# SCH_Syntheseproject_proof_of_concept_sen.net
KiCad netlist of a schematic drawn in EasyEDA
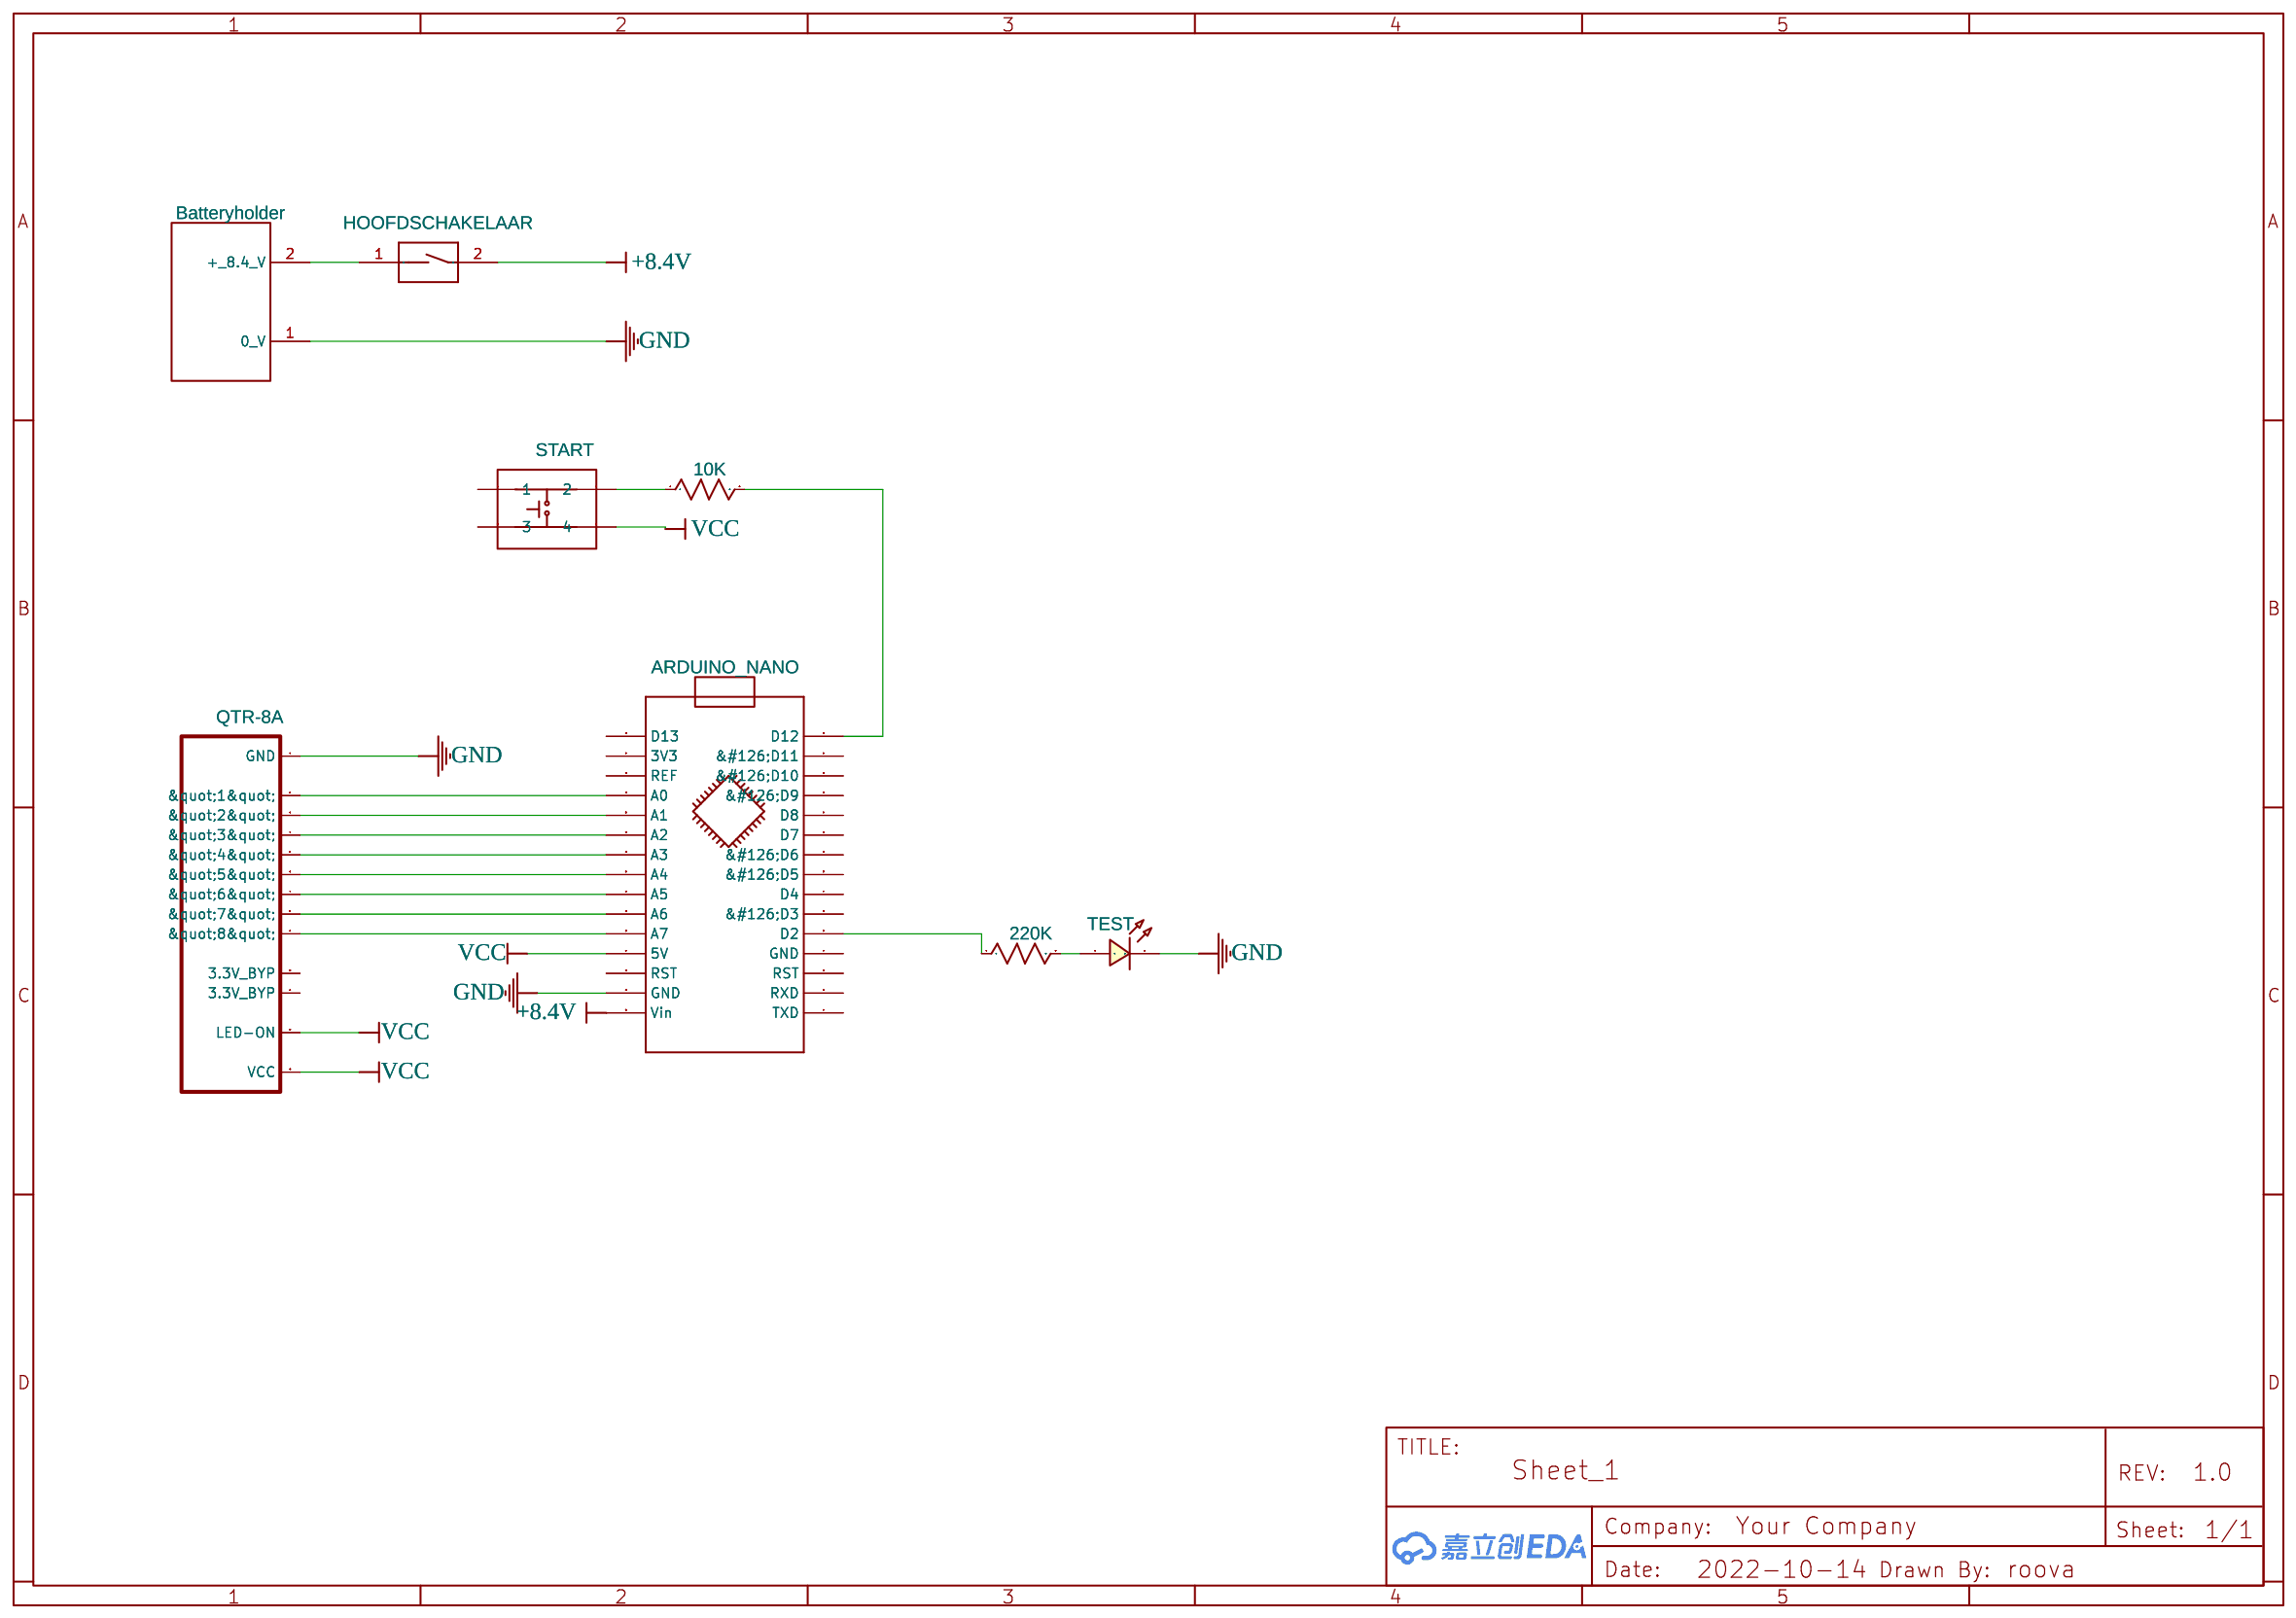
[diagram p0: schematic sheet]

(export (version "E")
  (design (tool "Eeschema 10.0.6"))
  (components
    (comp (ref "10K") (value "1k") (libsource (lib "") (part "R_0603_US_1")))
    (comp (ref "220K") (value "1k") (libsource (lib "") (part "R_0603_US")))
    (comp (ref "ARDUINO_NANO")
      (value "ARDUINO-NANO_V3")
      (fields (field (name "BOM_Manufacturer Part") "ARDUINO-NANO_AK"))
      (libsource (lib "") (part "ARDUINO-NANO_V3"))
    )
    (comp (ref "HOOFDSCHAKELAAR")
      (value "DIP1")
      (fields
        (field (name "BOM_Manufacturer Part") "A6TN-1101")
        (field (name "BOM_Supplier Part") "Z12167-ND")
      )
      (libsource (lib "") (part "DIP1"))
    )
    (comp (ref "START")
      (value "PUSHBUTTON 6X6X4.5 4 PINS COPY")
      (fields (field (name "BOM_Manufacturer Part") "sparkfun"))
      (libsource (lib "") (part "PUSHBUTTON 6X6X4.5 4 PINS COPY"))
    )
    (comp (ref "TEST")
      (value "LED-0603_R")
      (fields
        (field (name "BOM_Manufacturer Part") "19-217/R6C-AL1M2VY/3T")
        (field (name "BOM_Supplier Part") "C72044")
      )
      (libsource (lib "") (part "LED-0603_R"))
    )
    (comp (ref "U2")
      (value "QTR-8A")
      (fields (field (name "BOM_Supplier Part") "960"))
      (libsource (lib "") (part "QTR-8A"))
    )
    (comp (ref "U4") (value "Batteryholder") (libsource (lib "") (part "Batteryholder")))
  )
  (nets
    (net (code "1") (name "+8.4V") (class "Default")
      (node (ref "ARDUINO_NANO") (pin "30") (pinfunction "Vin_30") (pintype "unspecified"))
      (node (ref "HOOFDSCHAKELAAR") (pin "2") (pinfunction "2_2") (pintype "unspecified"))
    )
    (net (code "2") (name "GND") (class "Default")
      (node (ref "ARDUINO_NANO") (pin "29") (pinfunction "GND_29") (pintype "unspecified"))
      (node (ref "TEST") (pin "2") (pinfunction "2_2") (pintype "unspecified"))
      (node (ref "U2") (pin "1") (pinfunction "GND_1") (pintype "unspecified"))
      (node (ref "U4") (pin "1") (pinfunction "0_V_1") (pintype "unspecified"))
    )
    (net (code "3") (name "Net-(10K-Pad1)") (class "Default")
      (node (ref "10K") (pin "1") (pinfunction "1_1") (pintype "unspecified"))
      (node (ref "START") (pin "2") (pinfunction "2_2") (pintype "unspecified"))
    )
    (net (code "4") (name "Net-(220K-Pad2)") (class "Default")
      (node (ref "220K") (pin "2") (pinfunction "2_2") (pintype "unspecified"))
      (node (ref "TEST") (pin "1") (pinfunction "1_1") (pintype "unspecified"))
    )
    (net (code "5") (name "Net-(ARDUINO_NANO-A0)") (class "Default")
      (node (ref "ARDUINO_NANO") (pin "19") (pinfunction "A0_19") (pintype "unspecified"))
      (node (ref "U2") (pin "2") (pinfunction "&quot;1&quot;_2") (pintype "unspecified"))
    )
    (net (code "6") (name "Net-(ARDUINO_NANO-A1)") (class "Default")
      (node (ref "ARDUINO_NANO") (pin "20") (pinfunction "A1_20") (pintype "unspecified"))
      (node (ref "U2") (pin "3") (pinfunction "&quot;2&quot;_3") (pintype "unspecified"))
    )
    (net (code "7") (name "Net-(ARDUINO_NANO-A2)") (class "Default")
      (node (ref "ARDUINO_NANO") (pin "21") (pinfunction "A2_21") (pintype "unspecified"))
      (node (ref "U2") (pin "4") (pinfunction "&quot;3&quot;_4") (pintype "unspecified"))
    )
    (net (code "8") (name "Net-(ARDUINO_NANO-A3)") (class "Default")
      (node (ref "ARDUINO_NANO") (pin "22") (pinfunction "A3_22") (pintype "unspecified"))
      (node (ref "U2") (pin "5") (pinfunction "&quot;4&quot;_5") (pintype "unspecified"))
    )
    (net (code "9") (name "Net-(ARDUINO_NANO-A4)") (class "Default")
      (node (ref "ARDUINO_NANO") (pin "23") (pinfunction "A4_23") (pintype "unspecified"))
      (node (ref "U2") (pin "6") (pinfunction "&quot;5&quot;_6") (pintype "unspecified"))
    )
    (net (code "10") (name "Net-(ARDUINO_NANO-A5)") (class "Default")
      (node (ref "ARDUINO_NANO") (pin "24") (pinfunction "A5_24") (pintype "unspecified"))
      (node (ref "U2") (pin "7") (pinfunction "&quot;6&quot;_7") (pintype "unspecified"))
    )
    (net (code "11") (name "Net-(ARDUINO_NANO-A6)") (class "Default")
      (node (ref "ARDUINO_NANO") (pin "25") (pinfunction "A6_25") (pintype "unspecified"))
      (node (ref "U2") (pin "8") (pinfunction "&quot;7&quot;_8") (pintype "unspecified"))
    )
    (net (code "12") (name "Net-(ARDUINO_NANO-A7)") (class "Default")
      (node (ref "ARDUINO_NANO") (pin "26") (pinfunction "A7_26") (pintype "unspecified"))
      (node (ref "U2") (pin "9") (pinfunction "&quot;8&quot;_9") (pintype "unspecified"))
    )
    (net (code "13") (name "Net-(ARDUINO_NANO-D2)") (class "Default")
      (node (ref "220K") (pin "1") (pinfunction "1_1") (pintype "unspecified"))
      (node (ref "ARDUINO_NANO") (pin "5") (pinfunction "D2_5") (pintype "unspecified"))
    )
    (net (code "14") (name "Net-(ARDUINO_NANO-D12)") (class "Default")
      (node (ref "10K") (pin "2") (pinfunction "2_2") (pintype "unspecified"))
      (node (ref "ARDUINO_NANO") (pin "15") (pinfunction "D12_15") (pintype "unspecified"))
    )
    (net (code "15") (name "Net-(U4-+_8.4_V)") (class "Default")
      (node (ref "HOOFDSCHAKELAAR") (pin "1") (pinfunction "1_1") (pintype "unspecified"))
      (node (ref "U4") (pin "2") (pinfunction "+_8.4_V_2") (pintype "unspecified"))
    )
    (net (code "16") (name "VCC") (class "Default")
      (node (ref "ARDUINO_NANO") (pin "27") (pinfunction "5V_27") (pintype "unspecified"))
      (node (ref "START") (pin "4") (pinfunction "4_4") (pintype "unspecified"))
      (node (ref "U2") (pin "12") (pinfunction "LED-ON_12") (pintype "unspecified"))
    )
    (net (code "17") (name "unconnected-(ARDUINO_NANO-&#126;D3-Pad6)") (class "Default")
      (node (ref "ARDUINO_NANO") (pin "6") (pinfunction "&#126;D3_6") (pintype "unspecified"))
    )
    (net (code "18") (name "unconnected-(ARDUINO_NANO-&#126;D5-Pad8)") (class "Default")
      (node (ref "ARDUINO_NANO") (pin "8") (pinfunction "&#126;D5_8") (pintype "unspecified"))
    )
    (net (code "19") (name "unconnected-(ARDUINO_NANO-&#126;D6-Pad9)") (class "Default")
      (node (ref "ARDUINO_NANO") (pin "9") (pinfunction "&#126;D6_9") (pintype "unspecified"))
    )
    (net (code "20") (name "unconnected-(ARDUINO_NANO-&#126;D9-Pad12)") (class "Default")
      (node (ref "ARDUINO_NANO") (pin "12") (pinfunction "&#126;D9_12") (pintype "unspecified"))
    )
    (net (code "21") (name "unconnected-(ARDUINO_NANO-&#126;D10-Pad13)") (class "Default")
      (node (ref "ARDUINO_NANO") (pin "13") (pinfunction "&#126;D10_13") (pintype "unspecified"))
    )
    (net (code "22") (name "unconnected-(ARDUINO_NANO-&#126;D11-Pad14)") (class "Default")
      (node (ref "ARDUINO_NANO") (pin "14") (pinfunction "&#126;D11_14") (pintype "unspecified"))
    )
    (net (code "23") (name "unconnected-(ARDUINO_NANO-3V3-Pad17)") (class "Default")
      (node (ref "ARDUINO_NANO") (pin "17") (pinfunction "3V3_17") (pintype "unspecified"))
    )
    (net (code "24") (name "unconnected-(ARDUINO_NANO-D4-Pad7)") (class "Default")
      (node (ref "ARDUINO_NANO") (pin "7") (pinfunction "D4_7") (pintype "unspecified"))
    )
    (net (code "25") (name "unconnected-(ARDUINO_NANO-D7-Pad10)") (class "Default")
      (node (ref "ARDUINO_NANO") (pin "10") (pinfunction "D7_10") (pintype "unspecified"))
    )
    (net (code "26") (name "unconnected-(ARDUINO_NANO-D8-Pad11)") (class "Default")
      (node (ref "ARDUINO_NANO") (pin "11") (pinfunction "D8_11") (pintype "unspecified"))
    )
    (net (code "27") (name "unconnected-(ARDUINO_NANO-D13-Pad16)") (class "Default")
      (node (ref "ARDUINO_NANO") (pin "16") (pinfunction "D13_16") (pintype "unspecified"))
    )
    (net (code "28") (name "unconnected-(ARDUINO_NANO-GND-Pad4)") (class "Default")
      (node (ref "ARDUINO_NANO") (pin "4") (pinfunction "GND_4") (pintype "unspecified"))
    )
    (net (code "29") (name "unconnected-(ARDUINO_NANO-REF-Pad18)") (class "Default")
      (node (ref "ARDUINO_NANO") (pin "18") (pinfunction "REF_18") (pintype "unspecified"))
    )
    (net (code "30") (name "unconnected-(ARDUINO_NANO-RST-Pad3)") (class "Default")
      (node (ref "ARDUINO_NANO") (pin "3") (pinfunction "RST_3") (pintype "unspecified"))
    )
    (net (code "31") (name "unconnected-(ARDUINO_NANO-RST-Pad28)") (class "Default")
      (node (ref "ARDUINO_NANO") (pin "28") (pinfunction "RST_28") (pintype "unspecified"))
    )
    (net (code "32") (name "unconnected-(ARDUINO_NANO-RXD-Pad2)") (class "Default")
      (node (ref "ARDUINO_NANO") (pin "2") (pinfunction "RXD_2") (pintype "unspecified"))
    )
    (net (code "33") (name "unconnected-(ARDUINO_NANO-TXD-Pad1)") (class "Default")
      (node (ref "ARDUINO_NANO") (pin "1") (pinfunction "TXD_1") (pintype "unspecified"))
    )
    (net (code "34") (name "unconnected-(START-Pad1)") (class "Default")
      (node (ref "START") (pin "1") (pinfunction "1_1") (pintype "unspecified"))
    )
    (net (code "35") (name "unconnected-(START-Pad3)") (class "Default")
      (node (ref "START") (pin "3") (pinfunction "3_3") (pintype "unspecified"))
    )
    (net (code "36") (name "unconnected-(U2-3.3V_BYP-Pad10)") (class "Default")
      (node (ref "U2") (pin "10") (pinfunction "3.3V_BYP_10") (pintype "unspecified"))
    )
    (net (code "37") (name "unconnected-(U2-3.3V_BYP-Pad11)") (class "Default")
      (node (ref "U2") (pin "11") (pinfunction "3.3V_BYP_11") (pintype "unspecified"))
    )
  )
)
